# smoothieboard-alt-p0.net
KiCad netlist of a schematic drawn in Altium Designer
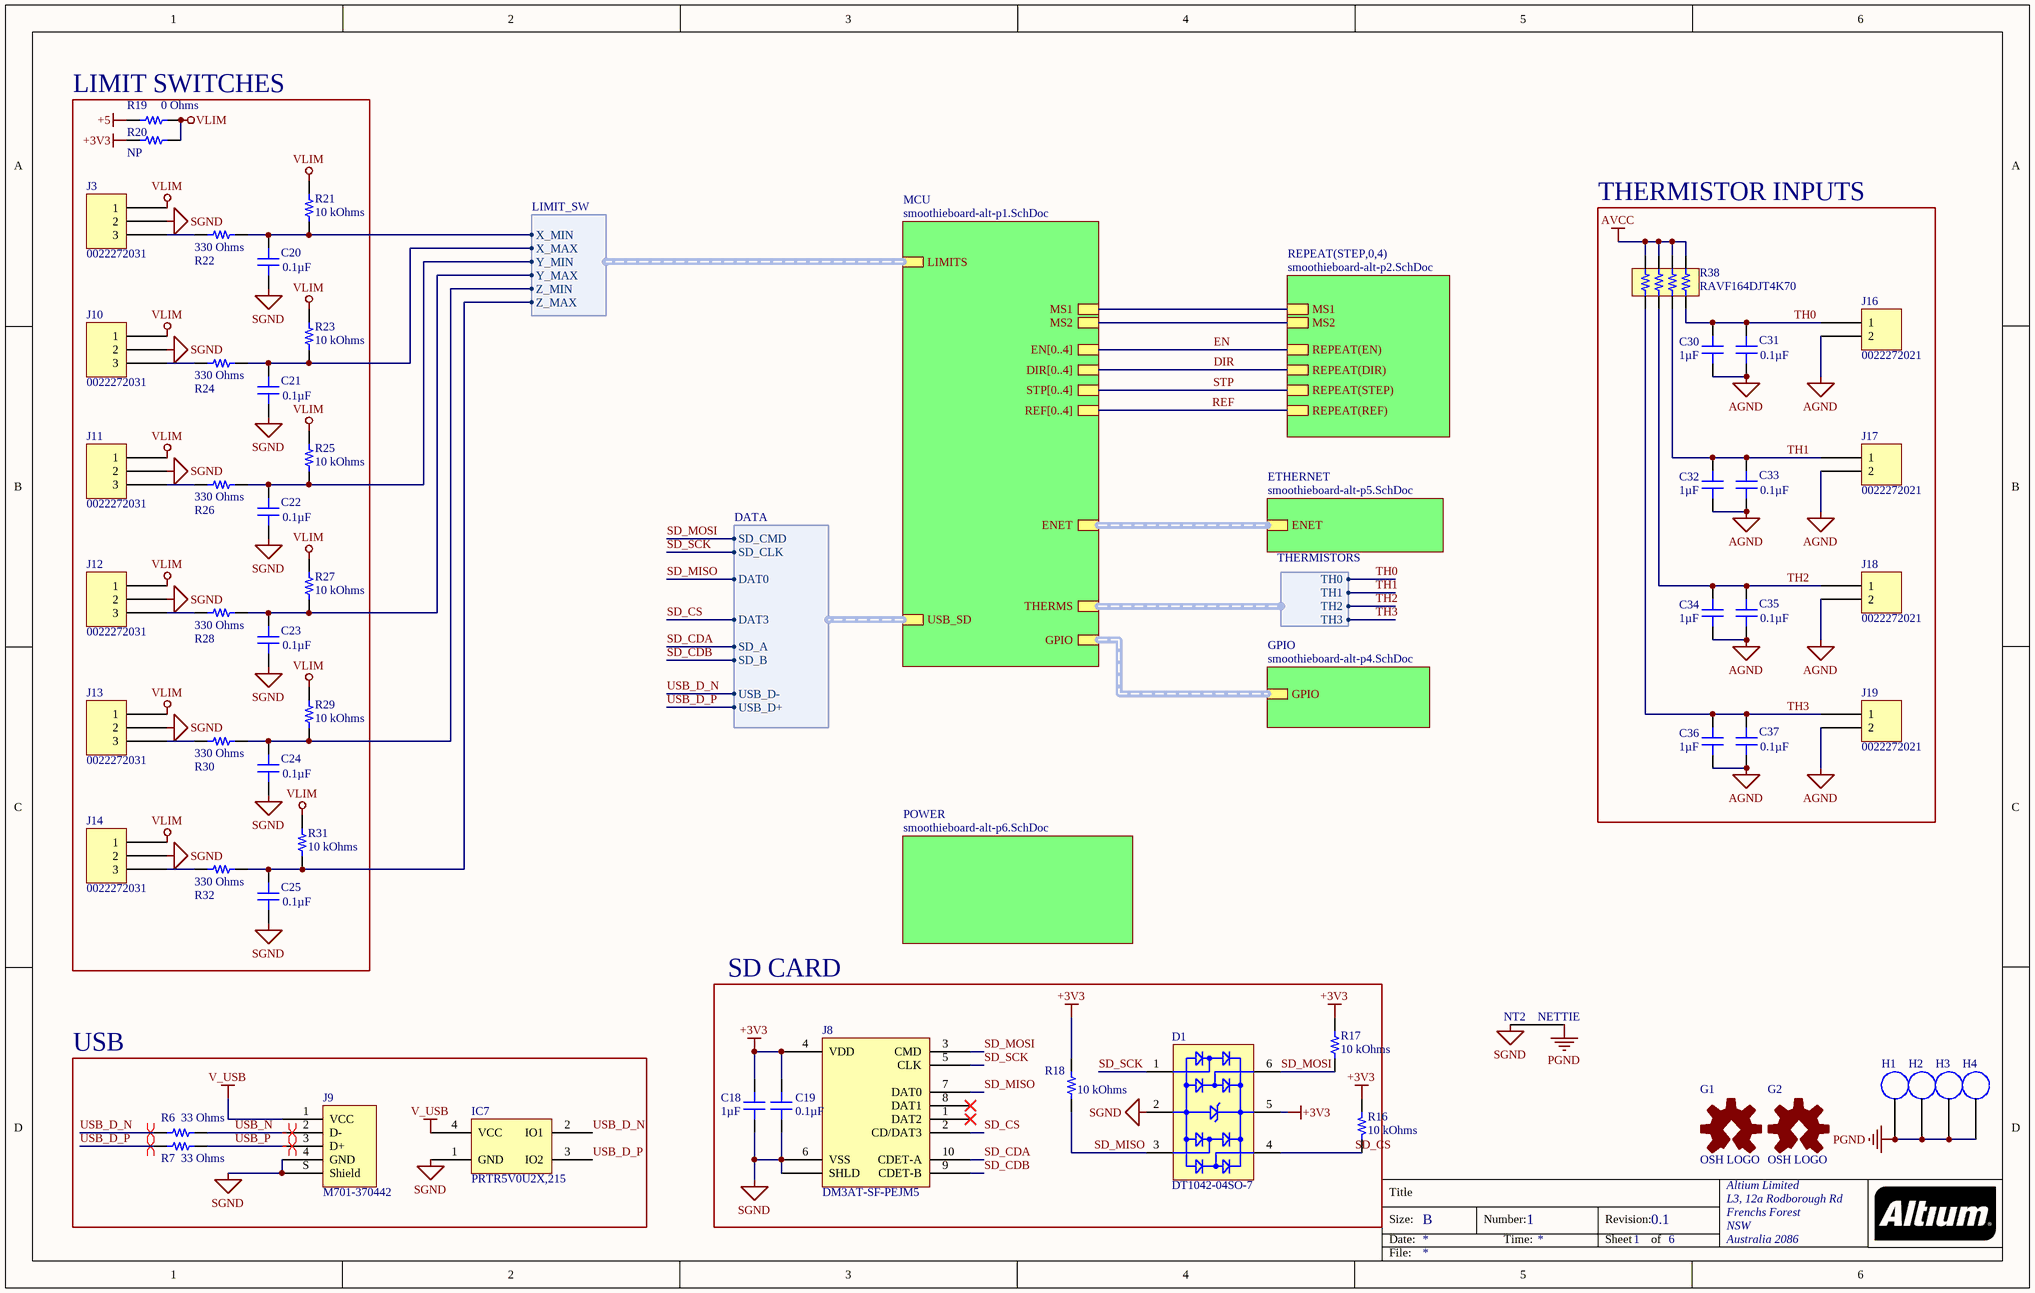
[diagram p0: smoothieboard-alt-p0.SchDoc]

(export (version "E")
  (design (tool "Eeschema 10.0.6"))
  (components
    (comp (ref "C18")
      (value "1µF")
      (footprint "CAP 0603_1608")
      (description "CAP CER 1UF 6.3V X7R 0603")
      (fields
        (field (name "PART NUMBER") "CL10B105KQ8NNNC")
        (field (name "MANUFACTURER") "Samsung Electro-Mechanics")
      )
      (libsource (lib "CAL") (part "Capacitor"))
    )
    (comp (ref "C19")
      (value "0.1µF")
      (footprint "CAP 0402_1005")
      (description "CAP CER 0.1UF 6.3V X5R 0402")
      (fields (field (name "PART NUMBER") "CC0402MRX5R5BB104") (field (name "MANUFACTURER") "Yageo"))
      (libsource (lib "CAL") (part "Capacitor"))
    )
    (comp (ref "C20")
      (value "0.1µF")
      (footprint "CAP 0402_1005")
      (description "CAP CER 0.1UF 6.3V X5R 0402")
      (fields (field (name "PART NUMBER") "CC0402MRX5R5BB104") (field (name "MANUFACTURER") "Yageo"))
      (libsource (lib "CAL") (part "Capacitor"))
    )
    (comp (ref "C21")
      (value "0.1µF")
      (footprint "CAP 0402_1005")
      (description "CAP CER 0.1UF 6.3V X5R 0402")
      (fields (field (name "PART NUMBER") "CC0402MRX5R5BB104") (field (name "MANUFACTURER") "Yageo"))
      (libsource (lib "CAL") (part "Capacitor"))
    )
    (comp (ref "C22")
      (value "0.1µF")
      (footprint "CAP 0402_1005")
      (description "CAP CER 0.1UF 6.3V X5R 0402")
      (fields (field (name "PART NUMBER") "CC0402MRX5R5BB104") (field (name "MANUFACTURER") "Yageo"))
      (libsource (lib "CAL") (part "Capacitor"))
    )
    (comp (ref "C23")
      (value "0.1µF")
      (footprint "CAP 0402_1005")
      (description "CAP CER 0.1UF 6.3V X5R 0402")
      (fields (field (name "PART NUMBER") "CC0402MRX5R5BB104") (field (name "MANUFACTURER") "Yageo"))
      (libsource (lib "CAL") (part "Capacitor"))
    )
    (comp (ref "C24")
      (value "0.1µF")
      (footprint "CAP 0402_1005")
      (description "CAP CER 0.1UF 6.3V X5R 0402")
      (fields (field (name "PART NUMBER") "CC0402MRX5R5BB104") (field (name "MANUFACTURER") "Yageo"))
      (libsource (lib "CAL") (part "Capacitor"))
    )
    (comp (ref "C25")
      (value "0.1µF")
      (footprint "CAP 0402_1005")
      (description "CAP CER 0.1UF 6.3V X5R 0402")
      (fields (field (name "PART NUMBER") "CC0402MRX5R5BB104") (field (name "MANUFACTURER") "Yageo"))
      (libsource (lib "CAL") (part "Capacitor"))
    )
    (comp (ref "C30")
      (value "1µF")
      (footprint "CAP 0603_1608")
      (description "CAP CER 1UF 6.3V X7R 0603")
      (fields
        (field (name "PART NUMBER") "CL10B105KQ8NNNC")
        (field (name "MANUFACTURER") "Samsung Electro-Mechanics")
      )
      (libsource (lib "CAL") (part "Capacitor"))
    )
    (comp (ref "C31")
      (value "0.1µF")
      (footprint "CAP 0402_1005")
      (description "CAP CER 0.1UF 6.3V X5R 0402")
      (fields (field (name "PART NUMBER") "CC0402MRX5R5BB104") (field (name "MANUFACTURER") "Yageo"))
      (libsource (lib "CAL") (part "Capacitor"))
    )
    (comp (ref "C32")
      (value "1µF")
      (footprint "CAP 0603_1608")
      (description "CAP CER 1UF 6.3V X7R 0603")
      (fields
        (field (name "PART NUMBER") "CL10B105KQ8NNNC")
        (field (name "MANUFACTURER") "Samsung Electro-Mechanics")
      )
      (libsource (lib "CAL") (part "Capacitor"))
    )
    (comp (ref "C33")
      (value "0.1µF")
      (footprint "CAP 0402_1005")
      (description "CAP CER 0.1UF 6.3V X5R 0402")
      (fields (field (name "PART NUMBER") "CC0402MRX5R5BB104") (field (name "MANUFACTURER") "Yageo"))
      (libsource (lib "CAL") (part "Capacitor"))
    )
    (comp (ref "C34")
      (value "1µF")
      (footprint "CAP 0603_1608")
      (description "CAP CER 1UF 6.3V X7R 0603")
      (fields
        (field (name "PART NUMBER") "CL10B105KQ8NNNC")
        (field (name "MANUFACTURER") "Samsung Electro-Mechanics")
      )
      (libsource (lib "CAL") (part "Capacitor"))
    )
    (comp (ref "C35")
      (value "0.1µF")
      (footprint "CAP 0402_1005")
      (description "CAP CER 0.1UF 6.3V X5R 0402")
      (fields (field (name "PART NUMBER") "CC0402MRX5R5BB104") (field (name "MANUFACTURER") "Yageo"))
      (libsource (lib "CAL") (part "Capacitor"))
    )
    (comp (ref "C36")
      (value "1µF")
      (footprint "CAP 0603_1608")
      (description "CAP CER 1UF 6.3V X7R 0603")
      (fields
        (field (name "PART NUMBER") "CL10B105KQ8NNNC")
        (field (name "MANUFACTURER") "Samsung Electro-Mechanics")
      )
      (libsource (lib "CAL") (part "Capacitor"))
    )
    (comp (ref "C37")
      (value "0.1µF")
      (footprint "CAP 0402_1005")
      (description "CAP CER 0.1UF 6.3V X5R 0402")
      (fields (field (name "PART NUMBER") "CC0402MRX5R5BB104") (field (name "MANUFACTURER") "Yageo"))
      (libsource (lib "CAL") (part "Capacitor"))
    )
    (comp (ref "D1")
      (value "DT1042-04SO-7")
      (footprint "DIODES SOT-23-6 W6")
      (description "TVS DIODE 5V 9V SOT26")
      (fields (field (name "MANUFACTURER") "Diodes Incorporated"))
      (libsource (lib "CAL") (part "DIODES SOT-23-6"))
    )
    (comp (ref "G1")
      (value "OSH LOGO")
      (footprint "OSH_LOGO")
      (description "Open source hardware logo")
      (libsource (lib "smoothie-lib") (part "OSH_LOGO"))
    )
    (comp (ref "G2")
      (value "OSH LOGO")
      (footprint "OSH_LOGO")
      (description "Open source hardware logo")
      (libsource (lib "smoothie-lib") (part "OSH_LOGO"))
    )
    (comp (ref "H1")
      (value "PTH")
      (footprint "PTH-M3.5")
      (description "Plated thru-hole.")
      (libsource (lib "smoothie-lib") (part "PTH"))
    )
    (comp (ref "H2")
      (value "PTH")
      (footprint "PTH-M3.5")
      (description "Plated thru-hole.")
      (libsource (lib "smoothie-lib") (part "PTH"))
    )
    (comp (ref "H3")
      (value "PTH")
      (footprint "PTH-M3.5")
      (description "Plated thru-hole.")
      (libsource (lib "smoothie-lib") (part "PTH"))
    )
    (comp (ref "H4")
      (value "PTH")
      (footprint "PTH-M3.5")
      (description "Plated thru-hole.")
      (libsource (lib "smoothie-lib") (part "PTH"))
    )
    (comp (ref "IC7")
      (value "PRTR5V0U2X,215")
      (footprint "SOT143B")
      (description "TVS DIODE 5.5V SOT143B")
      (fields (field (name "MANUFACTURER") "Nexperia USA Inc."))
      (libsource (lib "CAL") (part "NXP PRTR5V0U2X"))
    )
    (comp (ref "J3")
      (value "0022272031")
      (footprint "MOLEX KK 0022272031")
      (description "CONN HEADER VERT 3POS 2.54MM")
      (fields (field (name "MANUFACTURER") "Molex"))
      (libsource (lib "CAL") (part "3 Pin"))
    )
    (comp (ref "J8")
      (value "DM3AT-SF-PEJM5")
      (footprint "HIROSE DM3AT-SF-PEJM5")
      (description "CONN MICRO SD CARD PUSH-PUSH R/A")
      (fields (field (name "MANUFACTURER") "Hirose Electric Co Ltd"))
      (libsource (lib "CAL") (part "Hirose DM3 MicroSD"))
    )
    (comp (ref "J9")
      (value "M701-370442")
      (footprint "HARWIN USB M701-370442")
      (description "CONN RCPT USB2.0 TYPEB 4P SMD RA")
      (fields (field (name "MANUFACTURER") "Harwin Inc."))
      (libsource (lib "CAL") (part "USB 2.0 Type B"))
    )
    (comp (ref "J10")
      (value "0022272031")
      (footprint "MOLEX KK 0022272031")
      (description "CONN HEADER VERT 3POS 2.54MM")
      (fields (field (name "MANUFACTURER") "Molex"))
      (libsource (lib "CAL") (part "3 Pin"))
    )
    (comp (ref "J11")
      (value "0022272031")
      (footprint "MOLEX KK 0022272031")
      (description "CONN HEADER VERT 3POS 2.54MM")
      (fields (field (name "MANUFACTURER") "Molex"))
      (libsource (lib "CAL") (part "3 Pin"))
    )
    (comp (ref "J12")
      (value "0022272031")
      (footprint "MOLEX KK 0022272031")
      (description "CONN HEADER VERT 3POS 2.54MM")
      (fields (field (name "MANUFACTURER") "Molex"))
      (libsource (lib "CAL") (part "3 Pin"))
    )
    (comp (ref "J13")
      (value "0022272031")
      (footprint "MOLEX KK 0022272031")
      (description "CONN HEADER VERT 3POS 2.54MM")
      (fields (field (name "MANUFACTURER") "Molex"))
      (libsource (lib "CAL") (part "3 Pin"))
    )
    (comp (ref "J14")
      (value "0022272031")
      (footprint "MOLEX KK 0022272031")
      (description "CONN HEADER VERT 3POS 2.54MM")
      (fields (field (name "MANUFACTURER") "Molex"))
      (libsource (lib "CAL") (part "3 Pin"))
    )
    (comp (ref "J16")
      (value "0022272021")
      (footprint "MOLEX KK 0022272021")
      (description "CONN HEADER VERT 2POS 2.54MM")
      (fields (field (name "MANUFACTURER") "Molex"))
      (libsource (lib "CAL") (part "2 Pin"))
    )
    (comp (ref "J17")
      (value "0022272021")
      (footprint "MOLEX KK 0022272021")
      (description "CONN HEADER VERT 2POS 2.54MM")
      (fields (field (name "MANUFACTURER") "Molex"))
      (libsource (lib "CAL") (part "2 Pin"))
    )
    (comp (ref "J18")
      (value "0022272021")
      (footprint "MOLEX KK 0022272021")
      (description "CONN HEADER VERT 2POS 2.54MM")
      (fields (field (name "MANUFACTURER") "Molex"))
      (libsource (lib "CAL") (part "2 Pin"))
    )
    (comp (ref "J19")
      (value "0022272021")
      (footprint "MOLEX KK 0022272021")
      (description "CONN HEADER VERT 2POS 2.54MM")
      (fields (field (name "MANUFACTURER") "Molex"))
      (libsource (lib "CAL") (part "2 Pin"))
    )
    (comp (ref "NT2")
      (value "NETTIE")
      (footprint "NETTIE")
      (description "Net tie point.")
      (libsource (lib "smoothie-lib") (part "NETTIE"))
    )
    (comp (ref "R6")
      (value "33 Ohms")
      (footprint "RES 0402_1005")
      (description "RES 33 OHM 1% 1/16W 0402")
      (fields (field (name "PART NUMBER") "SFR01MZPF33R0") (field (name "MANUFACTURER") "Rohm Semiconductor"))
      (libsource (lib "CAL") (part "Resistor"))
    )
    (comp (ref "R7")
      (value "33 Ohms")
      (footprint "RES 0402_1005")
      (description "RES 33 OHM 1% 1/16W 0402")
      (fields (field (name "PART NUMBER") "SFR01MZPF33R0") (field (name "MANUFACTURER") "Rohm Semiconductor"))
      (libsource (lib "CAL") (part "Resistor"))
    )
    (comp (ref "R16")
      (value "10 kOhms")
      (footprint "RES 0402_1005")
      (description "RES SMD 10K OHM 5% 1/16W 0402")
      (fields (field (name "PART NUMBER") "CRCW040210K0JNTD") (field (name "MANUFACTURER") "Vishay Dale"))
      (libsource (lib "CAL") (part "Resistor"))
    )
    (comp (ref "R17")
      (value "10 kOhms")
      (footprint "RES 0402_1005")
      (description "RES SMD 10K OHM 5% 1/16W 0402")
      (fields (field (name "PART NUMBER") "CRCW040210K0JNTD") (field (name "MANUFACTURER") "Vishay Dale"))
      (libsource (lib "CAL") (part "Resistor"))
    )
    (comp (ref "R18")
      (value "10 kOhms")
      (footprint "RES 0402_1005")
      (description "RES SMD 10K OHM 5% 1/16W 0402")
      (fields (field (name "PART NUMBER") "CRCW040210K0JNTD") (field (name "MANUFACTURER") "Vishay Dale"))
      (libsource (lib "CAL") (part "Resistor"))
    )
    (comp (ref "R19")
      (value "0 Ohms")
      (footprint "RES 0603_1608")
      (description "RES SMD 0 OHM JUMPER 1/4W 0603")
      (fields (field (name "PART NUMBER") "CRCW06030000Z0EAHP") (field (name "MANUFACTURER") "Vishay Dale"))
      (libsource (lib "CAL") (part "Resistor"))
    )
    (comp (ref "R20")
      (value "NP")
      (footprint "RES 0603_1608")
      (description "RES SMD 0 OHM JUMPER 1/4W 0603")
      (fields (field (name "PART NUMBER") "CRCW06030000Z0EAHP") (field (name "MANUFACTURER") "Vishay Dale"))
      (libsource (lib "CAL") (part "Resistor"))
    )
    (comp (ref "R21")
      (value "10 kOhms")
      (footprint "RES 0603_1608")
      (description "RES SMD 10K OHM 5% 1/4W 0603")
      (fields (field (name "PART NUMBER") "RCS060310K0JNEA") (field (name "MANUFACTURER") "Vishay Dale"))
      (libsource (lib "CAL") (part "Resistor"))
    )
    (comp (ref "R22")
      (value "330 Ohms")
      (footprint "RES 0603_1608")
      (description "RES SMD 330 OHM 5% 1/10W 0603")
      (fields
        (field (name "PART NUMBER") "ERJ-3GEYJ331V")
        (field (name "MANUFACTURER") "Panasonic Electronic Components")
      )
      (libsource (lib "CAL") (part "Resistor"))
    )
    (comp (ref "R23")
      (value "10 kOhms")
      (footprint "RES 0603_1608")
      (description "RES SMD 10K OHM 5% 1/4W 0603")
      (fields (field (name "PART NUMBER") "RCS060310K0JNEA") (field (name "MANUFACTURER") "Vishay Dale"))
      (libsource (lib "CAL") (part "Resistor"))
    )
    (comp (ref "R24")
      (value "330 Ohms")
      (footprint "RES 0603_1608")
      (description "RES SMD 330 OHM 5% 1/10W 0603")
      (fields
        (field (name "PART NUMBER") "ERJ-3GEYJ331V")
        (field (name "MANUFACTURER") "Panasonic Electronic Components")
      )
      (libsource (lib "CAL") (part "Resistor"))
    )
    (comp (ref "R25")
      (value "10 kOhms")
      (footprint "RES 0603_1608")
      (description "RES SMD 10K OHM 5% 1/4W 0603")
      (fields (field (name "PART NUMBER") "RCS060310K0JNEA") (field (name "MANUFACTURER") "Vishay Dale"))
      (libsource (lib "CAL") (part "Resistor"))
    )
    (comp (ref "R26")
      (value "330 Ohms")
      (footprint "RES 0603_1608")
      (description "RES SMD 330 OHM 5% 1/10W 0603")
      (fields
        (field (name "PART NUMBER") "ERJ-3GEYJ331V")
        (field (name "MANUFACTURER") "Panasonic Electronic Components")
      )
      (libsource (lib "CAL") (part "Resistor"))
    )
    (comp (ref "R27")
      (value "10 kOhms")
      (footprint "RES 0603_1608")
      (description "RES SMD 10K OHM 5% 1/4W 0603")
      (fields (field (name "PART NUMBER") "RCS060310K0JNEA") (field (name "MANUFACTURER") "Vishay Dale"))
      (libsource (lib "CAL") (part "Resistor"))
    )
    (comp (ref "R28")
      (value "330 Ohms")
      (footprint "RES 0603_1608")
      (description "RES SMD 330 OHM 5% 1/10W 0603")
      (fields
        (field (name "PART NUMBER") "ERJ-3GEYJ331V")
        (field (name "MANUFACTURER") "Panasonic Electronic Components")
      )
      (libsource (lib "CAL") (part "Resistor"))
    )
    (comp (ref "R29")
      (value "10 kOhms")
      (footprint "RES 0603_1608")
      (description "RES SMD 10K OHM 5% 1/4W 0603")
      (fields (field (name "PART NUMBER") "RCS060310K0JNEA") (field (name "MANUFACTURER") "Vishay Dale"))
      (libsource (lib "CAL") (part "Resistor"))
    )
    (comp (ref "R30")
      (value "330 Ohms")
      (footprint "RES 0603_1608")
      (description "RES SMD 330 OHM 5% 1/10W 0603")
      (fields
        (field (name "PART NUMBER") "ERJ-3GEYJ331V")
        (field (name "MANUFACTURER") "Panasonic Electronic Components")
      )
      (libsource (lib "CAL") (part "Resistor"))
    )
    (comp (ref "R31")
      (value "10 kOhms")
      (footprint "RES 0603_1608")
      (description "RES SMD 10K OHM 5% 1/4W 0603")
      (fields (field (name "PART NUMBER") "RCS060310K0JNEA") (field (name "MANUFACTURER") "Vishay Dale"))
      (libsource (lib "CAL") (part "Resistor"))
    )
    (comp (ref "R32")
      (value "330 Ohms")
      (footprint "RES 0603_1608")
      (description "RES SMD 330 OHM 5% 1/10W 0603")
      (fields
        (field (name "PART NUMBER") "ERJ-3GEYJ331V")
        (field (name "MANUFACTURER") "Panasonic Electronic Components")
      )
      (libsource (lib "CAL") (part "Resistor"))
    )
    (comp (ref "R38")
      (value "RAVF164DJT4K70")
      (footprint "RESNET 1206-8 CONVEX")
      (description "RES ARRAY 4 RES 4.7K OHM 1206")
      (fields (field (name "MANUFACTURER") "Stackpole Electronics Inc") (field (name "TOLERANCE") "±5%"))
      (libsource (lib "CAL") (part "Resistor Array (4 circuit)"))
    )
  )
  (nets
    (net (code "4") (name "+3V3") (class "Default")
      (node (ref "C18") (pin "2") (pinfunction "2_2") (pintype "passive"))
      (node (ref "C19") (pin "2") (pinfunction "2_2") (pintype "passive"))
      (node (ref "D1") (pin "5") (pinfunction "VBUS_5") (pintype "passive"))
      (node (ref "J8") (pin "4") (pinfunction "VDD_4") (pintype "passive"))
      (node (ref "R16") (pin "1") (pinfunction "1_1") (pintype "passive"))
      (node (ref "R17") (pin "1") (pinfunction "1_1") (pintype "passive"))
      (node (ref "R18") (pin "1") (pinfunction "1_1") (pintype "passive"))
      (node (ref "R20") (pin "1") (pinfunction "1_1") (pintype "passive"))
    )
    (net (code "5") (name "+5") (class "Default")
      (node (ref "R19") (pin "1") (pinfunction "1_1") (pintype "passive"))
    )
    (net (code "16") (name "/SD_CDA") (class "Default")
      (node (ref "J8") (pin "10") (pinfunction "CDET-A_10") (pintype "passive"))
    )
    (net (code "17") (name "/SD_CDB") (class "Default")
      (node (ref "J8") (pin "9") (pinfunction "CDET-B_9") (pintype "passive"))
    )
    (net (code "18") (name "/SD_CS") (class "Default")
      (node (ref "D1") (pin "4") (pinfunction "I/O_3_4") (pintype "passive"))
      (node (ref "J8") (pin "2") (pinfunction "CD/DAT3_2") (pintype "passive"))
      (node (ref "R16") (pin "2") (pinfunction "2_2") (pintype "passive"))
    )
    (net (code "19") (name "/SD_MISO") (class "Default")
      (node (ref "D1") (pin "3") (pinfunction "I/O_2_3") (pintype "passive"))
      (node (ref "J8") (pin "7") (pinfunction "DAT0_7") (pintype "passive"))
      (node (ref "R18") (pin "2") (pinfunction "2_2") (pintype "passive"))
    )
    (net (code "20") (name "/SD_MOSI") (class "Default")
      (node (ref "D1") (pin "6") (pinfunction "I/O_4_6") (pintype "passive"))
      (node (ref "J8") (pin "3") (pinfunction "CMD_3") (pintype "passive"))
      (node (ref "R17") (pin "2") (pinfunction "2_2") (pintype "passive"))
    )
    (net (code "21") (name "/SD_SCK") (class "Default")
      (node (ref "D1") (pin "1") (pinfunction "I/O_1_1") (pintype "passive"))
      (node (ref "J8") (pin "5") (pinfunction "CLK_5") (pintype "passive"))
    )
    (net (code "24") (name "/TH0") (class "Default")
      (node (ref "C30") (pin "2") (pinfunction "2_2") (pintype "passive"))
      (node (ref "C31") (pin "2") (pinfunction "2_2") (pintype "passive"))
      (node (ref "J16") (pin "1") (pinfunction "1_1") (pintype "passive"))
      (node (ref "R38") (pin "4") (pinfunction "4_4") (pintype "passive"))
    )
    (net (code "25") (name "/TH1") (class "Default")
      (node (ref "C32") (pin "2") (pinfunction "2_2") (pintype "passive"))
      (node (ref "C33") (pin "2") (pinfunction "2_2") (pintype "passive"))
      (node (ref "J17") (pin "1") (pinfunction "1_1") (pintype "passive"))
      (node (ref "R38") (pin "3") (pinfunction "3_3") (pintype "passive"))
    )
    (net (code "26") (name "/TH2") (class "Default")
      (node (ref "C34") (pin "2") (pinfunction "2_2") (pintype "passive"))
      (node (ref "C35") (pin "2") (pinfunction "2_2") (pintype "passive"))
      (node (ref "J18") (pin "1") (pinfunction "1_1") (pintype "passive"))
      (node (ref "R38") (pin "2") (pinfunction "2_2") (pintype "passive"))
    )
    (net (code "27") (name "/TH3") (class "Default")
      (node (ref "C36") (pin "2") (pinfunction "2_2") (pintype "passive"))
      (node (ref "C37") (pin "2") (pinfunction "2_2") (pintype "passive"))
      (node (ref "J19") (pin "1") (pinfunction "1_1") (pintype "passive"))
      (node (ref "R38") (pin "1") (pinfunction "1_1") (pintype "passive"))
    )
    (net (code "28") (name "/USB_D_N") (class "Default")
      (node (ref "IC7") (pin "2") (pinfunction "IO1_2") (pintype "passive"))
      (node (ref "R6") (pin "1") (pinfunction "1_1") (pintype "passive"))
    )
    (net (code "29") (name "/USB_D_P") (class "Default")
      (node (ref "IC7") (pin "3") (pinfunction "IO2_3") (pintype "passive"))
      (node (ref "R7") (pin "1") (pinfunction "1_1") (pintype "passive"))
    )
    (net (code "30") (name "/USB_N") (class "Default")
      (node (ref "J9") (pin "2") (pinfunction "D-_2") (pintype "passive"))
      (node (ref "R6") (pin "2") (pinfunction "2_2") (pintype "passive"))
    )
    (net (code "31") (name "/USB_P") (class "Default")
      (node (ref "J9") (pin "3") (pinfunction "D+_3") (pintype "passive"))
      (node (ref "R7") (pin "2") (pinfunction "2_2") (pintype "passive"))
    )
    (net (code "35") (name "AGND") (class "Default")
      (node (ref "C30") (pin "1") (pinfunction "1_1") (pintype "passive"))
      (node (ref "C31") (pin "1") (pinfunction "1_1") (pintype "passive"))
      (node (ref "C32") (pin "1") (pinfunction "1_1") (pintype "passive"))
      (node (ref "C33") (pin "1") (pinfunction "1_1") (pintype "passive"))
      (node (ref "C34") (pin "1") (pinfunction "1_1") (pintype "passive"))
      (node (ref "C35") (pin "1") (pinfunction "1_1") (pintype "passive"))
      (node (ref "C36") (pin "1") (pinfunction "1_1") (pintype "passive"))
      (node (ref "C37") (pin "1") (pinfunction "1_1") (pintype "passive"))
      (node (ref "J16") (pin "2") (pinfunction "2_2") (pintype "passive"))
      (node (ref "J17") (pin "2") (pinfunction "2_2") (pintype "passive"))
      (node (ref "J18") (pin "2") (pinfunction "2_2") (pintype "passive"))
      (node (ref "J19") (pin "2") (pinfunction "2_2") (pintype "passive"))
    )
    (net (code "36") (name "AVCC") (class "Default")
      (node (ref "R38") (pin "5") (pinfunction "5_5") (pintype "passive"))
      (node (ref "R38") (pin "6") (pinfunction "6_6") (pintype "passive"))
      (node (ref "R38") (pin "7") (pinfunction "7_7") (pintype "passive"))
      (node (ref "R38") (pin "8") (pinfunction "8_8") (pintype "passive"))
    )
    (net (code "37") (name "Net-(C20-Pad2)") (class "Default")
      (node (ref "C20") (pin "2") (pinfunction "2_2") (pintype "passive"))
      (node (ref "R21") (pin "2") (pinfunction "2_2") (pintype "passive"))
      (node (ref "R22") (pin "1") (pinfunction "1_1") (pintype "passive"))
    )
    (net (code "38") (name "Net-(C21-Pad2)") (class "Default")
      (node (ref "C21") (pin "2") (pinfunction "2_2") (pintype "passive"))
      (node (ref "R23") (pin "2") (pinfunction "2_2") (pintype "passive"))
      (node (ref "R24") (pin "1") (pinfunction "1_1") (pintype "passive"))
    )
    (net (code "39") (name "Net-(C22-Pad2)") (class "Default")
      (node (ref "C22") (pin "2") (pinfunction "2_2") (pintype "passive"))
      (node (ref "R25") (pin "2") (pinfunction "2_2") (pintype "passive"))
      (node (ref "R26") (pin "1") (pinfunction "1_1") (pintype "passive"))
    )
    (net (code "40") (name "Net-(C23-Pad2)") (class "Default")
      (node (ref "C23") (pin "2") (pinfunction "2_2") (pintype "passive"))
      (node (ref "R27") (pin "2") (pinfunction "2_2") (pintype "passive"))
      (node (ref "R28") (pin "1") (pinfunction "1_1") (pintype "passive"))
    )
    (net (code "41") (name "Net-(C24-Pad2)") (class "Default")
      (node (ref "C24") (pin "2") (pinfunction "2_2") (pintype "passive"))
      (node (ref "R29") (pin "2") (pinfunction "2_2") (pintype "passive"))
      (node (ref "R30") (pin "1") (pinfunction "1_1") (pintype "passive"))
    )
    (net (code "42") (name "Net-(C25-Pad2)") (class "Default")
      (node (ref "C25") (pin "2") (pinfunction "2_2") (pintype "passive"))
      (node (ref "R31") (pin "2") (pinfunction "2_2") (pintype "passive"))
      (node (ref "R32") (pin "1") (pinfunction "1_1") (pintype "passive"))
    )
    (net (code "43") (name "Net-(J3-Pad3)") (class "Default")
      (node (ref "J3") (pin "3") (pinfunction "3_3") (pintype "passive"))
      (node (ref "R22") (pin "2") (pinfunction "2_2") (pintype "passive"))
    )
    (net (code "44") (name "Net-(J10-Pad3)") (class "Default")
      (node (ref "J10") (pin "3") (pinfunction "3_3") (pintype "passive"))
      (node (ref "R24") (pin "2") (pinfunction "2_2") (pintype "passive"))
    )
    (net (code "45") (name "Net-(J11-Pad3)") (class "Default")
      (node (ref "J11") (pin "3") (pinfunction "3_3") (pintype "passive"))
      (node (ref "R26") (pin "2") (pinfunction "2_2") (pintype "passive"))
    )
    (net (code "46") (name "Net-(J12-Pad3)") (class "Default")
      (node (ref "J12") (pin "3") (pinfunction "3_3") (pintype "passive"))
      (node (ref "R28") (pin "2") (pinfunction "2_2") (pintype "passive"))
    )
    (net (code "47") (name "Net-(J13-Pad3)") (class "Default")
      (node (ref "J13") (pin "3") (pinfunction "3_3") (pintype "passive"))
      (node (ref "R30") (pin "2") (pinfunction "2_2") (pintype "passive"))
    )
    (net (code "48") (name "Net-(J14-Pad3)") (class "Default")
      (node (ref "J14") (pin "3") (pinfunction "3_3") (pintype "passive"))
      (node (ref "R32") (pin "2") (pinfunction "2_2") (pintype "passive"))
    )
    (net (code "49") (name "PGND") (class "Default")
      (node (ref "H1") (pin "1") (pinfunction "1_1") (pintype "passive"))
      (node (ref "H2") (pin "1") (pinfunction "1_1") (pintype "passive"))
      (node (ref "H3") (pin "1") (pinfunction "1_1") (pintype "passive"))
      (node (ref "H4") (pin "1") (pinfunction "1_1") (pintype "passive"))
      (node (ref "NT2") (pin "2") (pinfunction "2_2") (pintype "passive"))
    )
    (net (code "50") (name "SGND") (class "Default")
      (node (ref "C18") (pin "1") (pinfunction "1_1") (pintype "passive"))
      (node (ref "C19") (pin "1") (pinfunction "1_1") (pintype "passive"))
      (node (ref "C20") (pin "1") (pinfunction "1_1") (pintype "passive"))
      (node (ref "C21") (pin "1") (pinfunction "1_1") (pintype "passive"))
      (node (ref "C22") (pin "1") (pinfunction "1_1") (pintype "passive"))
      (node (ref "C23") (pin "1") (pinfunction "1_1") (pintype "passive"))
      (node (ref "C24") (pin "1") (pinfunction "1_1") (pintype "passive"))
      (node (ref "C25") (pin "1") (pinfunction "1_1") (pintype "passive"))
      (node (ref "D1") (pin "2") (pinfunction "GND_2") (pintype "passive"))
      (node (ref "IC7") (pin "1") (pinfunction "GND_1") (pintype "passive"))
      (node (ref "J10") (pin "2") (pinfunction "2_2") (pintype "passive"))
      (node (ref "J11") (pin "2") (pinfunction "2_2") (pintype "passive"))
      (node (ref "J12") (pin "2") (pinfunction "2_2") (pintype "passive"))
      (node (ref "J13") (pin "2") (pinfunction "2_2") (pintype "passive"))
      (node (ref "J14") (pin "2") (pinfunction "2_2") (pintype "passive"))
      (node (ref "J3") (pin "2") (pinfunction "2_2") (pintype "passive"))
      (node (ref "J8") (pin "6") (pinfunction "VSS_6") (pintype "passive"))
      (node (ref "J8") (pin "S") (pinfunction "SHLD_S") (pintype "passive"))
      (node (ref "J9") (pin "4") (pinfunction "GND_4") (pintype "passive"))
      (node (ref "J9") (pin "S") (pinfunction "Shield_S") (pintype "passive"))
      (node (ref "NT2") (pin "1") (pinfunction "1_1") (pintype "passive"))
    )
    (net (code "51") (name "VLIM") (class "Default")
      (node (ref "J10") (pin "1") (pinfunction "1_1") (pintype "passive"))
      (node (ref "J11") (pin "1") (pinfunction "1_1") (pintype "passive"))
      (node (ref "J12") (pin "1") (pinfunction "1_1") (pintype "passive"))
      (node (ref "J13") (pin "1") (pinfunction "1_1") (pintype "passive"))
      (node (ref "J14") (pin "1") (pinfunction "1_1") (pintype "passive"))
      (node (ref "J3") (pin "1") (pinfunction "1_1") (pintype "passive"))
      (node (ref "R19") (pin "2") (pinfunction "2_2") (pintype "passive"))
      (node (ref "R20") (pin "2") (pinfunction "2_2") (pintype "passive"))
      (node (ref "R21") (pin "1") (pinfunction "1_1") (pintype "passive"))
      (node (ref "R23") (pin "1") (pinfunction "1_1") (pintype "passive"))
      (node (ref "R25") (pin "1") (pinfunction "1_1") (pintype "passive"))
      (node (ref "R27") (pin "1") (pinfunction "1_1") (pintype "passive"))
      (node (ref "R29") (pin "1") (pinfunction "1_1") (pintype "passive"))
      (node (ref "R31") (pin "1") (pinfunction "1_1") (pintype "passive"))
    )
    (net (code "52") (name "V_USB") (class "Default")
      (node (ref "IC7") (pin "4") (pinfunction "VCC_4") (pintype "passive"))
      (node (ref "J9") (pin "1") (pinfunction "VCC_1") (pintype "passive"))
    )
    (net (code "53") (name "unconnected-(J8-DAT1-Pad8)") (class "Default")
      (node (ref "J8") (pin "8") (pinfunction "DAT1_8") (pintype "passive+no_connect"))
    )
    (net (code "54") (name "unconnected-(J8-DAT2-Pad1)") (class "Default")
      (node (ref "J8") (pin "1") (pinfunction "DAT2_1") (pintype "passive+no_connect"))
    )
  )
)
